# 05_-_POWER_SUPPY.net
KiCad netlist of a schematic drawn in Altium Designer
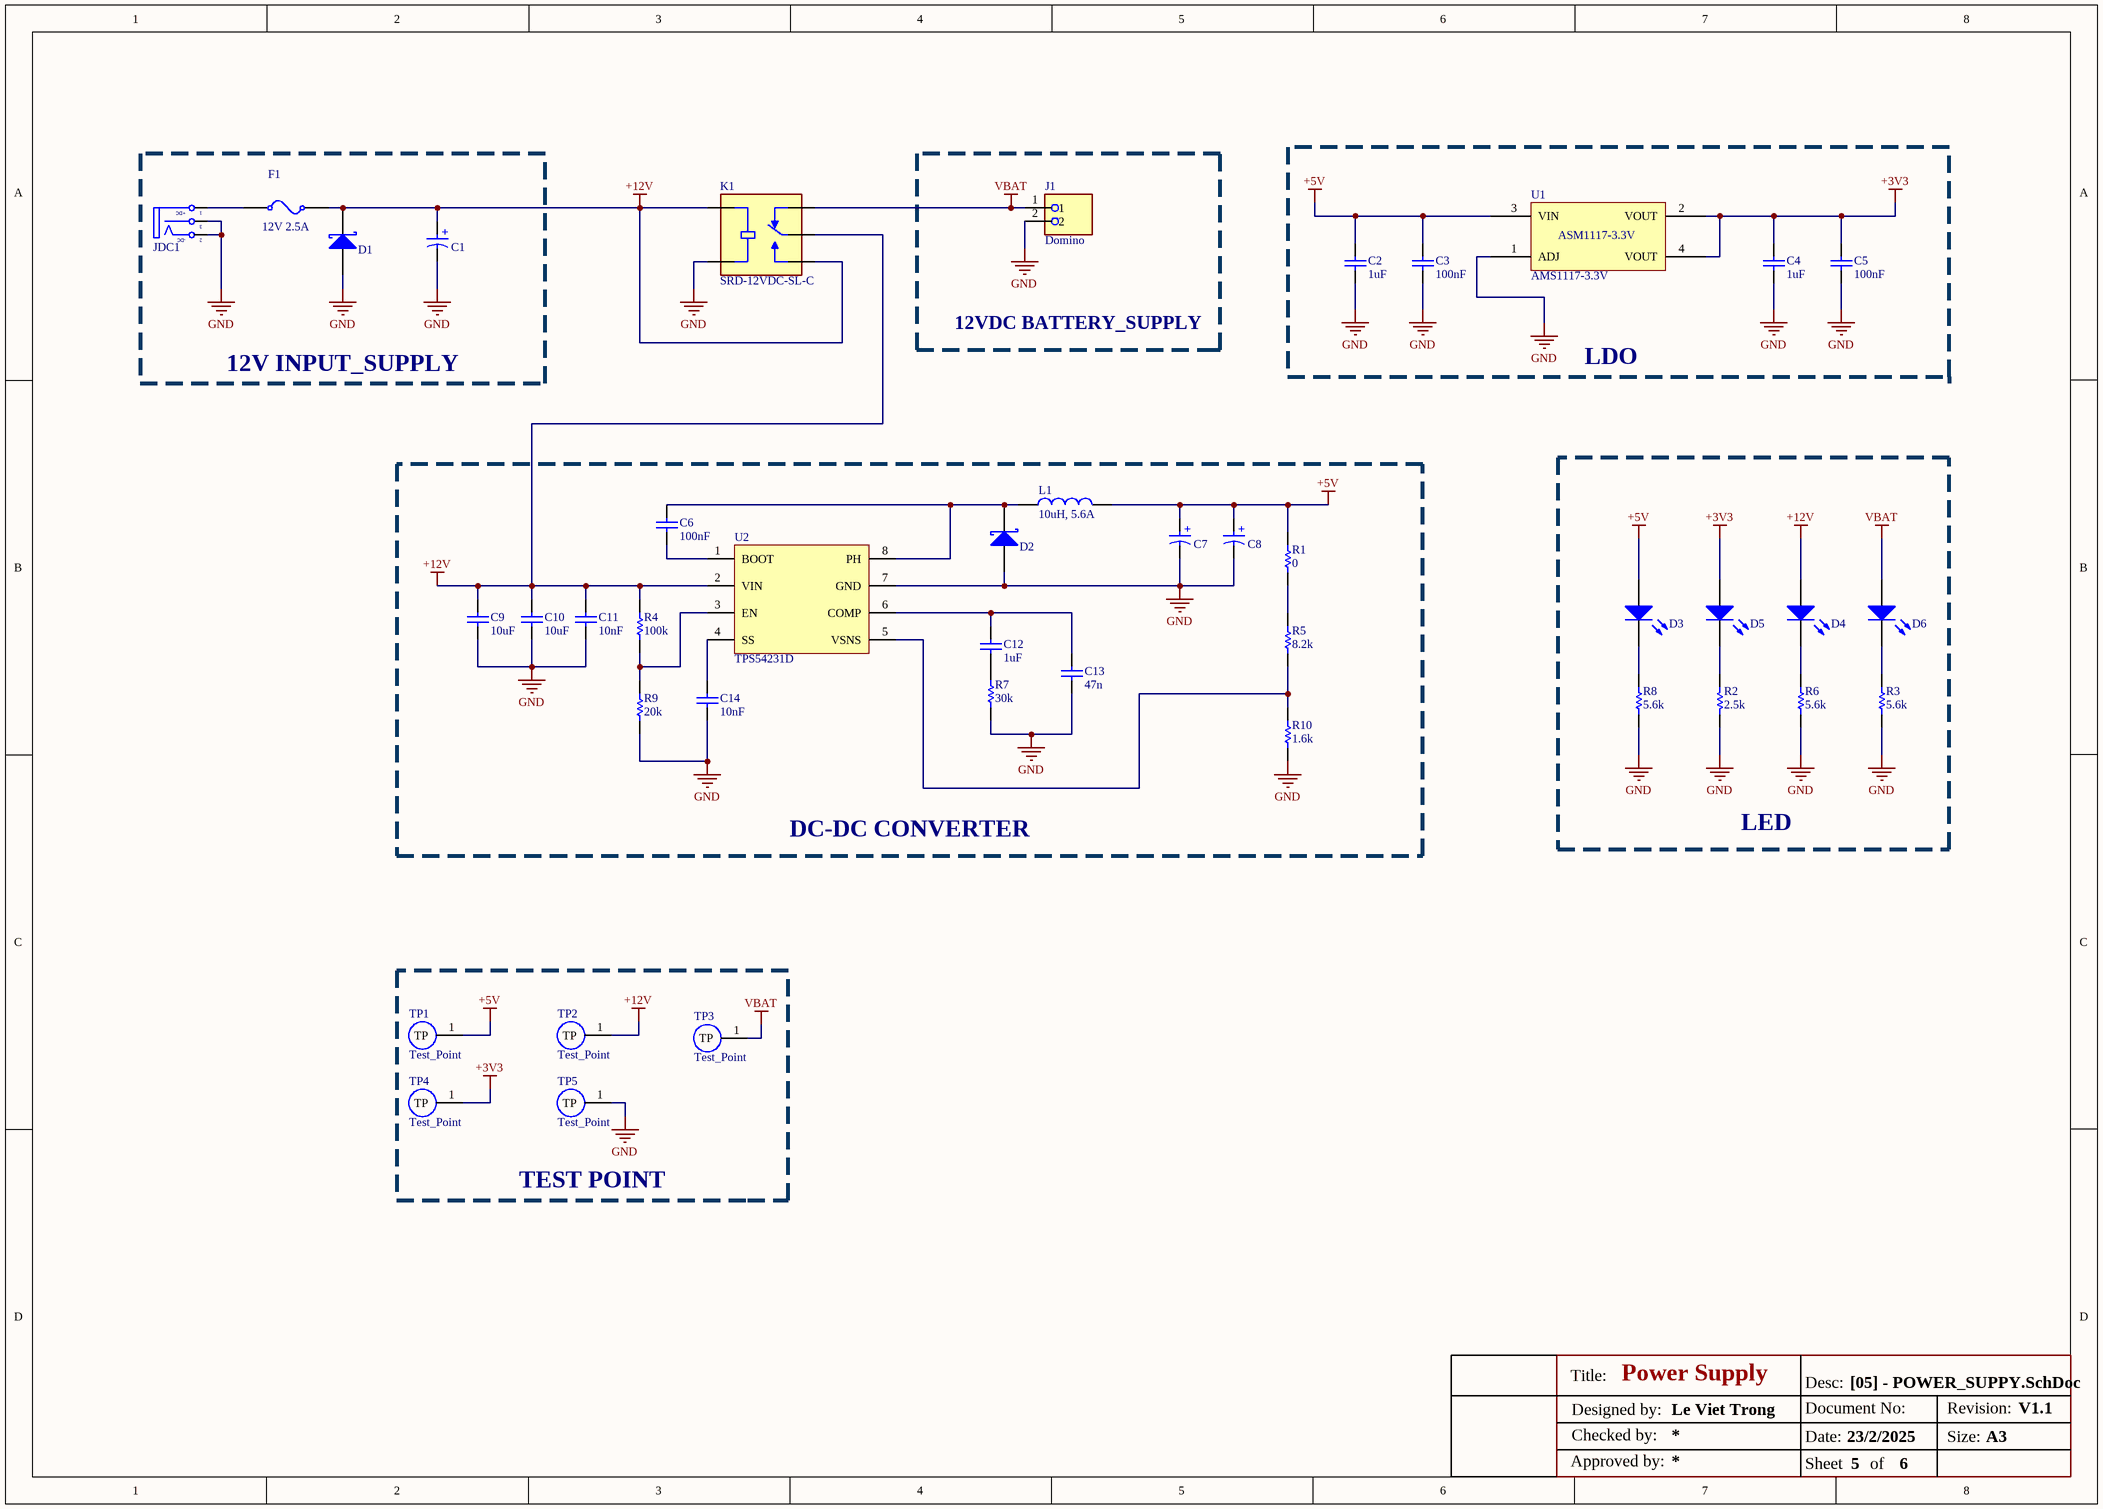
[diagram p0: [05] - POWER_SUPPY.SchDoc]

(export (version "E")
  (design (tool "Eeschema 10.0.6"))
  (components
    (comp (ref "C1")
      (value "47uF")
      (footprint "WCAP-ASLI_D4H5.5")
      (description "V-Chip, D4 x H5.5mm, 22uF, 16V")
      (libsource (lib "SMIOT_Lib_Schematic") (part "865080340003"))
    )
    (comp (ref "C2")
      (value "1uF")
      (footprint "CAP_0603")
      (description "CAP, size 0603, 1uF")
      (libsource (lib "SMIOT_Lib_Schematic") (part "01060310510"))
    )
    (comp (ref "C3")
      (value "100nF")
      (footprint "CAP_0603")
      (description "CAP, size 0603, 100nF")
      (libsource (lib "SMIOT_Lib_Schematic") (part "01060310410"))
    )
    (comp (ref "C4")
      (value "1uF")
      (footprint "CAP_0603")
      (description "CAP, size 0603, 1uF")
      (libsource (lib "SMIOT_Lib_Schematic") (part "01060310510"))
    )
    (comp (ref "C5")
      (value "100nF")
      (footprint "CAP_0603")
      (description "CAP, size 0603, 100nF")
      (libsource (lib "SMIOT_Lib_Schematic") (part "01060310410"))
    )
    (comp (ref "C6")
      (value "100nF")
      (footprint "CAP_0603")
      (description "CAP, size 0603, 100nF")
      (libsource (lib "SMIOT_Lib_Schematic") (part "01060310410"))
    )
    (comp (ref "C7")
      (value "47uF")
      (footprint "WCAP-ASLI_D5H5.5")
      (description "V-Chip, D5 x H5.5mm, 47uF, 16V")
      (libsource (lib "SMIOT_Lib_Schematic") (part "Tụ nhôm SMD"))
    )
    (comp (ref "C8")
      (value "47uF")
      (footprint "WCAP-ASLI_D5H5.5")
      (description "V-Chip, D5 x H5.5mm, 47uF, 16V")
      (libsource (lib "SMIOT_Lib_Schematic") (part "Tụ nhôm SMD"))
    )
    (comp (ref "C9")
      (value "10uF")
      (footprint "CAP_0603")
      (description "CAP, size 0603,10uF")
      (libsource (lib "SMIOT_Lib_Schematic") (part "01060310010"))
    )
    (comp (ref "C10")
      (value "10uF")
      (footprint "CAP_0603")
      (description "CAP, size 0603,10uF")
      (libsource (lib "SMIOT_Lib_Schematic") (part "01060310010"))
    )
    (comp (ref "C11")
      (value "10nF")
      (footprint "CAP_0603")
      (description "CAP, size 0603, 10nF")
      (libsource (lib "SMIOT_Lib_Schematic") (part "01060310310"))
    )
    (comp (ref "C12")
      (value "1uF")
      (footprint "CAP_0603")
      (description "CAP, size 0603, 1uF")
      (libsource (lib "SMIOT_Lib_Schematic") (part "01060310510"))
    )
    (comp (ref "C13")
      (value "47n")
      (footprint "CAP_0603")
      (description "CAP, size 0603, 47nF")
      (libsource (lib "SMIOT_Lib_Schematic") (part "01060347310"))
    )
    (comp (ref "C14")
      (value "10nF")
      (footprint "CAP_0603")
      (description "CAP, size 0603, 10nF")
      (libsource (lib "SMIOT_Lib_Schematic") (part "01060310310"))
    )
    (comp (ref "D1")
      (value "D Schottky")
      (footprint "SS34")
      (description "Schottky Diode")
      (fields (field (name "PUBLISHER") "Altium Limited"))
      (libsource (lib "Board_C24") (part "D Schottky"))
    )
    (comp (ref "D2")
      (value "D Schottky")
      (footprint "SS34")
      (description "Schottky Diode")
      (fields (field (name "PUBLISHER") "Altium Limited"))
      (libsource (lib "SMIOT_Lib_Schematic") (part "D Schottky"))
    )
    (comp (ref "D3")
      (value "LED SMD")
      (footprint "LED_0805_Blue")
      (description "LED")
      (libsource (lib "SMIOT_Lib_Schematic") (part "LED SMD"))
    )
    (comp (ref "D4")
      (value "LED SMD")
      (footprint "LED_0805_Blue")
      (description "LED")
      (libsource (lib "SMIOT_Lib_Schematic") (part "LED SMD"))
    )
    (comp (ref "D5")
      (value "LED SMD")
      (footprint "LED_0805_Blue")
      (description "LED")
      (libsource (lib "SMIOT_Lib_Schematic") (part "LED SMD"))
    )
    (comp (ref "D6")
      (value "LED SMD")
      (footprint "LED_0805_Blue")
      (description "LED")
      (libsource (lib "SMIOT_Lib_Schematic") (part "LED SMD"))
    )
    (comp (ref "F1")
      (value "12V 2.5A")
      (footprint "Fuse_SMD_1812")
      (description "Resettable Fuse, Size 1812, 8V, 2A")
      (fields (field (name "MANUFACTURER") "Littelfuse"))
      (libsource (lib "SMIOT_Lib_Schematic") (part "061812200008"))
    )
    (comp (ref "J1")
      (value "Domino")
      (footprint "PHOENIX_1935161")
      (description "PCB Terminal Screw 5mm 16AWG 400V 17.5A 2 Position COMBICON PT Series ¦ Phoenix Contact 1935161")
      (fields (field (name "MF") "Phoenix Contact") (field (name "MP") "1935161"))
      (libsource (lib "Domino") (part "Domino"))
    )
    (comp (ref "JDC1")
      (value "Jack DC")
      (footprint "DC-IN")
      (description "Jack DC input")
      (libsource (lib "SMIOT_Lib_Schematic") (part "Jack DC"))
    )
    (comp (ref "K1")
      (value "SRD-12VDC-SL-C")
      (footprint "RELAY_SRD-12VDC-SL-C")
      (description "General Purpose Non Latching 12VDC SPDT Through Hole Relays RoHS")
      (fields (field (name "MF") "Songle Relay"))
      (libsource (lib "RELAY") (part "SRD-12VDC-SL-C"))
    )
    (comp (ref "L1")
      (value "10uH, 5.6A")
      (footprint "WE-PD2A_5848")
      (description "WE-PD2A SMT Power Inductor, size 5848, 10uH, 2.2A")
      (fields
        (field (name "MANUFACTURER PART NUMBER") "78477410")
        (field (name "MANUFACTURER") "Wurth Elektronik")
      )
      (libsource (lib "SMIOT_Lib_Schematic") (part "78477410"))
    )
    (comp (ref "R1")
      (value "0")
      (footprint "resistor_0603")
      (description "RES, 0 Ohm, size 0603, 1%")
      (libsource (lib "SMIOT_Lib_Schematic") (part "0006030001"))
    )
    (comp (ref "R2")
      (value "2.5k")
      (footprint "resistor_0603")
      (description "RES, 2.5K Ohm, size 0603, 5%")
      (libsource (lib "SMIOT_Lib_Schematic") (part "0006032525"))
    )
    (comp (ref "R3")
      (value "5.6k")
      (footprint "resistor_0603")
      (description "RES, 5.6k Ohm, size 0603, 1%")
      (libsource (lib "SMIOT_Lib_Schematic") (part "0006035621"))
    )
    (comp (ref "R4")
      (value "100k")
      (footprint "resistor_0603")
      (description "RES, 100k Ohm, size 0603, 1%")
      (libsource (lib "SMIOT_Lib_Schematic") (part "0006031041"))
    )
    (comp (ref "R5")
      (value "8.2k")
      (footprint "resistor_0603")
      (description "RES, 8.2 kOhms, size 0603, 1%")
      (libsource (lib "SMIOT_Lib_Schematic") (part "0006038251"))
    )
    (comp (ref "R6")
      (value "5.6k")
      (footprint "resistor_0603")
      (description "RES, 5.6k Ohm, size 0603, 1%")
      (libsource (lib "SMIOT_Lib_Schematic") (part "0006035621"))
    )
    (comp (ref "R7")
      (value "30k")
      (footprint "resistor_0603")
      (description "RES, 30k Ohm, size 0603, 1%")
      (libsource (lib "SMIOT_Lib_Schematic") (part "0006033205"))
    )
    (comp (ref "R8")
      (value "5.6k")
      (footprint "resistor_0603")
      (description "RES, 5.6k Ohm, size 0603, 1%")
      (libsource (lib "SMIOT_Lib_Schematic") (part "0006035621"))
    )
    (comp (ref "R9")
      (value "20k")
      (footprint "resistor_0603")
      (description "RES, 20 kOhms, size 0603, 1%")
      (libsource (lib "SMIOT_Lib_Schematic") (part "0006032031"))
    )
    (comp (ref "R10")
      (value "1.6k")
      (footprint "resistor_0603")
      (description "RES, 1.5 kOhms, size 0603, 1%")
      (libsource (lib "SMIOT_Lib_Schematic") (part "0006031521"))
    )
    (comp (ref "TP1")
      (value "Test_Point")
      (footprint "TP_2MM")
      (description "Test point, 2mm radius")
      (libsource (lib "SMIOT_Lib_Schematic") (part "Test_Point"))
    )
    (comp (ref "TP2")
      (value "Test_Point")
      (footprint "TP_2MM")
      (description "Test point, 2mm radius")
      (libsource (lib "SMIOT_Lib_Schematic") (part "Test_Point"))
    )
    (comp (ref "TP3")
      (value "Test_Point")
      (footprint "TP_2MM")
      (description "Test point, 2mm radius")
      (libsource (lib "SMIOT_Lib_Schematic") (part "Test_Point"))
    )
    (comp (ref "TP4")
      (value "Test_Point")
      (footprint "TP_2MM")
      (description "Test point, 2mm radius")
      (libsource (lib "SMIOT_Lib_Schematic") (part "Test_Point"))
    )
    (comp (ref "TP5")
      (value "Test_Point")
      (footprint "TP_2MM")
      (description "Test point, 2mm radius")
      (libsource (lib "SMIOT_Lib_Schematic") (part "Test_Point"))
    )
    (comp (ref "U1")
      (value "AMS1117-3.3V")
      (footprint "AMS1117-3.3V SOT223")
      (description "AMS1117-3.3V, OUT 3.3V 1A.")
      (fields (field (name "MANUFACTURER") "AMS"))
      (libsource (lib "SMIOT_Lib_Schematic") (part "AMS1117-3.3V"))
    )
    (comp (ref "U2")
      (value "TPS54231D")
      (footprint "SOIC8")
      (description "Buck Switching Regulator IC Positive Adjustable 0.8V 1 Output 2A 8-SOIC (0.154\", 3.90mm Width)")
      (fields (field (name "MFR") "Texas Instruments"))
      (libsource (lib "SMIOT_Lib_Schematic") (part "TPS54231"))
    )
  )
  (nets
    (net (code "1") (name "+3V3") (class "Default")
      (node (ref "C4") (pin "2") (pinfunction "2_2") (pintype "passive"))
      (node (ref "C5") (pin "2") (pinfunction "2_2") (pintype "passive"))
      (node (ref "D5") (pin "1") (pinfunction "A_1") (pintype "passive"))
      (node (ref "TP4") (pin "1") (pinfunction "TP_1") (pintype "passive"))
      (node (ref "U1") (pin "2") (pinfunction "VOUT_2") (pintype "passive"))
      (node (ref "U1") (pin "4") (pinfunction "VOUT_4") (pintype "power_in"))
    )
    (net (code "2") (name "+5V") (class "Default")
      (node (ref "C2") (pin "2") (pinfunction "2_2") (pintype "passive"))
      (node (ref "C3") (pin "2") (pinfunction "2_2") (pintype "passive"))
      (node (ref "C7") (pin "1") (pinfunction "P_1") (pintype "passive"))
      (node (ref "C8") (pin "1") (pinfunction "P_1") (pintype "passive"))
      (node (ref "D3") (pin "1") (pinfunction "A_1") (pintype "passive"))
      (node (ref "L1") (pin "2") (pinfunction "2_2") (pintype "passive"))
      (node (ref "R1") (pin "2") (pinfunction "2_2") (pintype "passive"))
      (node (ref "TP1") (pin "1") (pinfunction "TP_1") (pintype "passive"))
      (node (ref "U1") (pin "3") (pinfunction "VIN_3") (pintype "passive"))
    )
    (net (code "3") (name "+12V") (class "Default")
      (node (ref "C1") (pin "1") (pinfunction "P_1") (pintype "passive"))
      (node (ref "C10") (pin "2") (pinfunction "2_2") (pintype "passive"))
      (node (ref "C11") (pin "2") (pinfunction "2_2") (pintype "passive"))
      (node (ref "C9") (pin "2") (pinfunction "2_2") (pintype "passive"))
      (node (ref "D1") (pin "2") (pinfunction "K_2") (pintype "passive"))
      (node (ref "D4") (pin "1") (pinfunction "A_1") (pintype "passive"))
      (node (ref "F1") (pin "1") (pinfunction "1_1") (pintype "passive"))
      (node (ref "K1") (pin "COIL1") (pinfunction "COIL1_COIL1") (pintype "passive"))
      (node (ref "K1") (pin "COM") (pinfunction "COM_COM") (pintype "passive"))
      (node (ref "K1") (pin "NO") (pinfunction "NO_NO") (pintype "passive"))
      (node (ref "R4") (pin "2") (pinfunction "2_2") (pintype "passive"))
      (node (ref "TP2") (pin "1") (pinfunction "TP_1") (pintype "passive"))
      (node (ref "U2") (pin "2") (pinfunction "VIN_2") (pintype "passive"))
    )
    (net (code "4") (name "GND") (class "Default")
      (node (ref "C1") (pin "2") (pinfunction "N_2") (pintype "passive"))
      (node (ref "C10") (pin "1") (pinfunction "1_1") (pintype "passive"))
      (node (ref "C11") (pin "1") (pinfunction "1_1") (pintype "passive"))
      (node (ref "C13") (pin "1") (pinfunction "1_1") (pintype "passive"))
      (node (ref "C14") (pin "1") (pinfunction "1_1") (pintype "passive"))
      (node (ref "C2") (pin "1") (pinfunction "1_1") (pintype "passive"))
      (node (ref "C3") (pin "1") (pinfunction "1_1") (pintype "passive"))
      (node (ref "C4") (pin "1") (pinfunction "1_1") (pintype "passive"))
      (node (ref "C5") (pin "1") (pinfunction "1_1") (pintype "passive"))
      (node (ref "C7") (pin "2") (pinfunction "N_2") (pintype "passive"))
      (node (ref "C8") (pin "2") (pinfunction "N_2") (pintype "passive"))
      (node (ref "C9") (pin "1") (pinfunction "1_1") (pintype "passive"))
      (node (ref "D1") (pin "1") (pinfunction "A_1") (pintype "passive"))
      (node (ref "D2") (pin "1") (pinfunction "A_1") (pintype "passive"))
      (node (ref "J1") (pin "2") (pinfunction "2_2") (pintype "passive"))
      (node (ref "JDC1") (pin "2") (pinfunction "TN_2") (pintype "passive"))
      (node (ref "JDC1") (pin "3") (pinfunction "S_3") (pintype "power_in"))
      (node (ref "K1") (pin "COIL2") (pinfunction "COIL2_COIL2") (pintype "passive"))
      (node (ref "R10") (pin "1") (pinfunction "1_1") (pintype "passive"))
      (node (ref "R2") (pin "1") (pinfunction "1_1") (pintype "passive"))
      (node (ref "R3") (pin "1") (pinfunction "1_1") (pintype "passive"))
      (node (ref "R6") (pin "1") (pinfunction "1_1") (pintype "passive"))
      (node (ref "R7") (pin "1") (pinfunction "1_1") (pintype "passive"))
      (node (ref "R8") (pin "1") (pinfunction "1_1") (pintype "passive"))
      (node (ref "R9") (pin "1") (pinfunction "1_1") (pintype "passive"))
      (node (ref "TP5") (pin "1") (pinfunction "TP_1") (pintype "passive"))
      (node (ref "U1") (pin "1") (pinfunction "ADJ_1") (pintype "power_in"))
      (node (ref "U2") (pin "7") (pinfunction "GND_7") (pintype "passive"))
    )
    (net (code "5") (name "Net-(C12-Pad2)") (class "Default")
      (node (ref "C12") (pin "2") (pinfunction "2_2") (pintype "passive"))
      (node (ref "R7") (pin "2") (pinfunction "2_2") (pintype "passive"))
    )
    (net (code "6") (name "Net-(D2-K)") (class "Default")
      (node (ref "C6") (pin "2") (pinfunction "2_2") (pintype "passive"))
      (node (ref "D2") (pin "2") (pinfunction "K_2") (pintype "passive"))
      (node (ref "L1") (pin "1") (pinfunction "1_1") (pintype "passive"))
      (node (ref "U2") (pin "8") (pinfunction "PH_8") (pintype "passive"))
    )
    (net (code "7") (name "Net-(D3-K)") (class "Default")
      (node (ref "D3") (pin "2") (pinfunction "K_2") (pintype "passive"))
      (node (ref "R8") (pin "2") (pinfunction "2_2") (pintype "passive"))
    )
    (net (code "8") (name "Net-(D4-K)") (class "Default")
      (node (ref "D4") (pin "2") (pinfunction "K_2") (pintype "passive"))
      (node (ref "R6") (pin "2") (pinfunction "2_2") (pintype "passive"))
    )
    (net (code "9") (name "Net-(D5-K)") (class "Default")
      (node (ref "D5") (pin "2") (pinfunction "K_2") (pintype "passive"))
      (node (ref "R2") (pin "2") (pinfunction "2_2") (pintype "passive"))
    )
    (net (code "10") (name "Net-(D6-K)") (class "Default")
      (node (ref "D6") (pin "2") (pinfunction "K_2") (pintype "passive"))
      (node (ref "R3") (pin "2") (pinfunction "2_2") (pintype "passive"))
    )
    (net (code "11") (name "Net-(JDC1-T)") (class "Default")
      (node (ref "F1") (pin "0") (pinfunction "0_0") (pintype "passive"))
      (node (ref "JDC1") (pin "1") (pinfunction "T_1") (pintype "passive"))
    )
    (net (code "12") (name "Net-(R1-Pad1)") (class "Default")
      (node (ref "R1") (pin "1") (pinfunction "1_1") (pintype "passive"))
      (node (ref "R5") (pin "2") (pinfunction "2_2") (pintype "passive"))
    )
    (net (code "13") (name "Net-(U2-BOOT)") (class "Default")
      (node (ref "C6") (pin "1") (pinfunction "1_1") (pintype "passive"))
      (node (ref "U2") (pin "1") (pinfunction "BOOT_1") (pintype "passive"))
    )
    (net (code "14") (name "Net-(U2-COMP)") (class "Default")
      (node (ref "C12") (pin "1") (pinfunction "1_1") (pintype "passive"))
      (node (ref "C13") (pin "2") (pinfunction "2_2") (pintype "passive"))
      (node (ref "U2") (pin "6") (pinfunction "COMP_6") (pintype "passive"))
    )
    (net (code "15") (name "Net-(U2-EN)") (class "Default")
      (node (ref "R4") (pin "1") (pinfunction "1_1") (pintype "passive"))
      (node (ref "R9") (pin "2") (pinfunction "2_2") (pintype "passive"))
      (node (ref "U2") (pin "3") (pinfunction "EN_3") (pintype "passive"))
    )
    (net (code "16") (name "Net-(U2-SS)") (class "Default")
      (node (ref "C14") (pin "2") (pinfunction "2_2") (pintype "passive"))
      (node (ref "U2") (pin "4") (pinfunction "SS_4") (pintype "passive"))
    )
    (net (code "17") (name "Net-(U2-VSNS)") (class "Default")
      (node (ref "R10") (pin "2") (pinfunction "2_2") (pintype "passive"))
      (node (ref "R5") (pin "1") (pinfunction "1_1") (pintype "passive"))
      (node (ref "U2") (pin "5") (pinfunction "VSNS_5") (pintype "passive"))
    )
    (net (code "18") (name "VBAT") (class "Default")
      (node (ref "D6") (pin "1") (pinfunction "A_1") (pintype "passive"))
      (node (ref "J1") (pin "1") (pinfunction "1_1") (pintype "passive"))
      (node (ref "K1") (pin "NC") (pinfunction "NC_NC") (pintype "passive"))
      (node (ref "TP3") (pin "1") (pinfunction "TP_1") (pintype "passive"))
    )
  )
)
